# Radio.net
KiCad netlist of a schematic drawn in Altium Designer
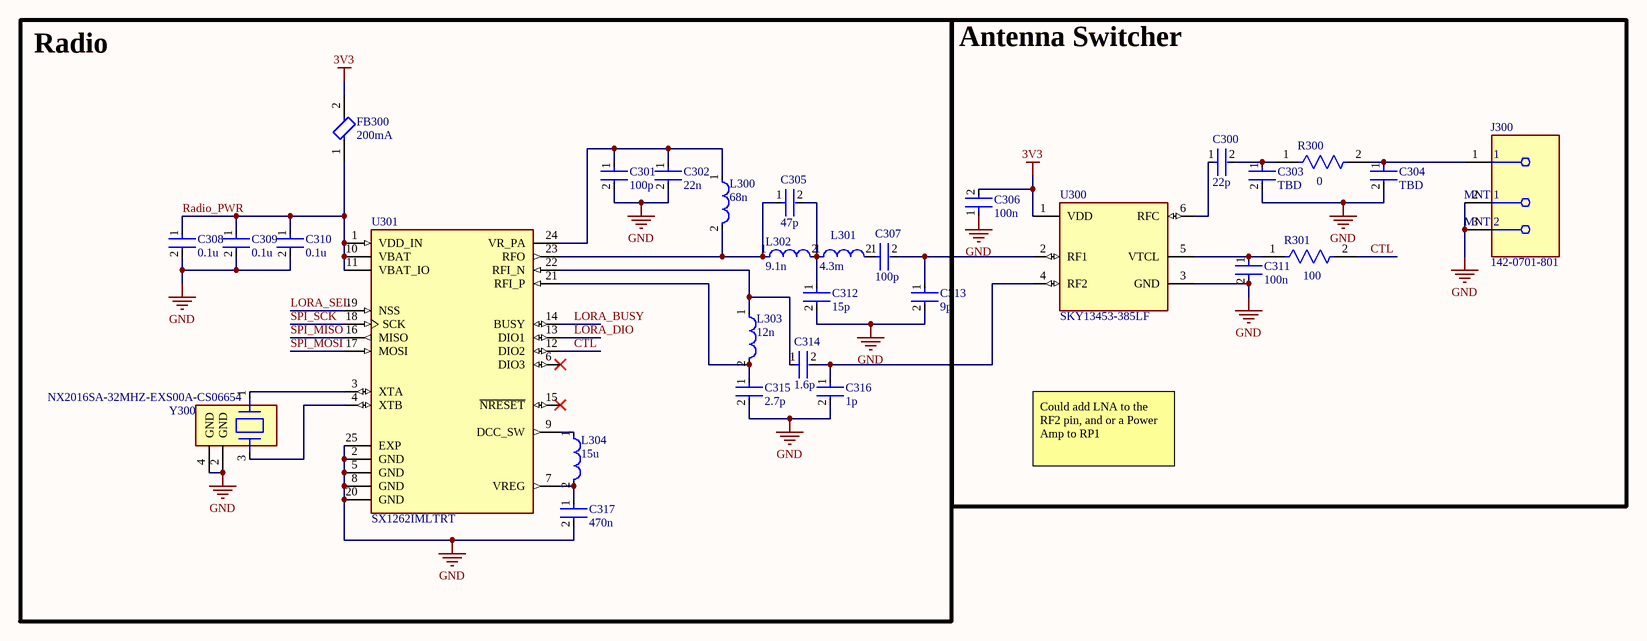
[diagram p0: Radio.SchDoc]

(export (version "E")
  (design (tool "Eeschema 10.0.6"))
  (components
    (comp (ref "C300")
      (value "CL10C681JB8NFNC")
      (footprint "FP-CL10-IPC_A")
      (description "Cap Ceramic 680pF 50V C0G ±5% Pad SMD 0603 +125°C T/R")
      (fields (field (name "CAPACITANCE") "22p") (field (name "TOLERANCE") "5%"))
      (libsource (lib "Altium Content Vault") (part "b4654b650e69147ec39a6b967a45e02"))
    )
    (comp (ref "C301")
      (value "CL10C681JB8NFNC")
      (footprint "FP-CL10-IPC_A")
      (description "Cap Ceramic 680pF 50V C0G ±5% Pad SMD 0603 +125°C T/R")
      (fields (field (name "CAPACITANCE") "100p") (field (name "TOLERANCE") "5%"))
      (libsource (lib "Altium Content Vault") (part "b4654b650e69147ec39a6b967a45e02"))
    )
    (comp (ref "C302")
      (value "CL10C681JB8NFNC")
      (footprint "FP-CL10-IPC_A")
      (description "Cap Ceramic 680pF 50V C0G ±5% Pad SMD 0603 +125°C T/R")
      (fields (field (name "CAPACITANCE") "22n") (field (name "TOLERANCE") "5%"))
      (libsource (lib "Altium Content Vault") (part "b4654b650e69147ec39a6b967a45e02"))
    )
    (comp (ref "C303")
      (value "CL10C681JB8NFNC")
      (footprint "FP-CL10-IPC_A")
      (description "Cap Ceramic 680pF 50V C0G ±5% Pad SMD 0603 +125°C T/R")
      (fields (field (name "CAPACITANCE") "TBD") (field (name "TOLERANCE") "5%"))
      (libsource (lib "Altium Content Vault") (part "b4654b650e69147ec39a6b967a45e02"))
    )
    (comp (ref "C304")
      (value "CL10C681JB8NFNC")
      (footprint "FP-CL10-IPC_A")
      (description "Cap Ceramic 680pF 50V C0G ±5% Pad SMD 0603 +125°C T/R")
      (fields (field (name "CAPACITANCE") "TBD") (field (name "TOLERANCE") "5%"))
      (libsource (lib "Altium Content Vault") (part "b4654b650e69147ec39a6b967a45e02"))
    )
    (comp (ref "C305")
      (value "CL10C681JB8NFNC")
      (footprint "FP-CL10-IPC_A")
      (description "Cap Ceramic 680pF 50V C0G ±5% Pad SMD 0603 +125°C T/R")
      (fields (field (name "CAPACITANCE") "47p") (field (name "TOLERANCE") "5%"))
      (libsource (lib "Altium Content Vault") (part "b4654b650e69147ec39a6b967a45e02"))
    )
    (comp (ref "C306")
      (value "CL10C681JB8NFNC")
      (footprint "FP-CL10-IPC_A")
      (description "Cap Ceramic 680pF 50V C0G ±5% Pad SMD 0603 +125°C T/R")
      (fields (field (name "CAPACITANCE") "100n") (field (name "TOLERANCE") "5%"))
      (libsource (lib "Altium Content Vault") (part "b4654b650e69147ec39a6b967a45e02"))
    )
    (comp (ref "C307")
      (value "CL10C681JB8NFNC")
      (footprint "FP-CL10-IPC_A")
      (description "Cap Ceramic 680pF 50V C0G ±5% Pad SMD 0603 +125°C T/R")
      (fields (field (name "CAPACITANCE") "100p") (field (name "TOLERANCE") "5%"))
      (libsource (lib "Altium Content Vault") (part "b4654b650e69147ec39a6b967a45e02"))
    )
    (comp (ref "C308")
      (value "CL10C681JB8NFNC")
      (footprint "FP-CL10-IPC_A")
      (description "Cap Ceramic 680pF 50V C0G ±5% Pad SMD 0603 +125°C T/R")
      (fields (field (name "CAPACITANCE") "0.1u") (field (name "TOLERANCE") "5%"))
      (libsource (lib "Altium Content Vault") (part "b4654b650e69147ec39a6b967a45e02"))
    )
    (comp (ref "C309")
      (value "CL10C681JB8NFNC")
      (footprint "FP-CL10-IPC_A")
      (description "Cap Ceramic 680pF 50V C0G ±5% Pad SMD 0603 +125°C T/R")
      (fields (field (name "CAPACITANCE") "0.1u") (field (name "TOLERANCE") "5%"))
      (libsource (lib "Altium Content Vault") (part "b4654b650e69147ec39a6b967a45e02"))
    )
    (comp (ref "C310")
      (value "CL10C681JB8NFNC")
      (footprint "FP-CL10-IPC_A")
      (description "Cap Ceramic 680pF 50V C0G ±5% Pad SMD 0603 +125°C T/R")
      (fields (field (name "CAPACITANCE") "0.1u") (field (name "TOLERANCE") "5%"))
      (libsource (lib "Altium Content Vault") (part "b4654b650e69147ec39a6b967a45e02"))
    )
    (comp (ref "C311")
      (value "CL10C681JB8NFNC")
      (footprint "FP-CL10-IPC_A")
      (description "Cap Ceramic 680pF 50V C0G ±5% Pad SMD 0603 +125°C T/R")
      (fields (field (name "CAPACITANCE") "100n") (field (name "TOLERANCE") "5%"))
      (libsource (lib "Altium Content Vault") (part "b4654b650e69147ec39a6b967a45e02"))
    )
    (comp (ref "C312")
      (value "CL10C681JB8NFNC")
      (footprint "FP-CL10-IPC_A")
      (description "Cap Ceramic 680pF 50V C0G ±5% Pad SMD 0603 +125°C T/R")
      (fields (field (name "CAPACITANCE") "15p") (field (name "TOLERANCE") "5%"))
      (libsource (lib "Altium Content Vault") (part "b4654b650e69147ec39a6b967a45e02"))
    )
    (comp (ref "C313")
      (value "CL10C681JB8NFNC")
      (footprint "FP-CL10-IPC_A")
      (description "Cap Ceramic 680pF 50V C0G ±5% Pad SMD 0603 +125°C T/R")
      (fields (field (name "CAPACITANCE") "9p") (field (name "TOLERANCE") "5%"))
      (libsource (lib "Altium Content Vault") (part "b4654b650e69147ec39a6b967a45e02"))
    )
    (comp (ref "C314")
      (value "CL10C681JB8NFNC")
      (footprint "FP-CL10-IPC_A")
      (description "Cap Ceramic 680pF 50V C0G ±5% Pad SMD 0603 +125°C T/R")
      (fields (field (name "CAPACITANCE") "1.6p") (field (name "TOLERANCE") "5%"))
      (libsource (lib "Altium Content Vault") (part "b4654b650e69147ec39a6b967a45e02"))
    )
    (comp (ref "C315")
      (value "CL10C681JB8NFNC")
      (footprint "FP-CL10-IPC_A")
      (description "Cap Ceramic 680pF 50V C0G ±5% Pad SMD 0603 +125°C T/R")
      (fields (field (name "CAPACITANCE") "2.7p") (field (name "TOLERANCE") "5%"))
      (libsource (lib "Altium Content Vault") (part "b4654b650e69147ec39a6b967a45e02"))
    )
    (comp (ref "C316")
      (value "CL10C681JB8NFNC")
      (footprint "FP-CL10-IPC_A")
      (description "Cap Ceramic 680pF 50V C0G ±5% Pad SMD 0603 +125°C T/R")
      (fields (field (name "CAPACITANCE") "1p") (field (name "TOLERANCE") "5%"))
      (libsource (lib "Altium Content Vault") (part "b4654b650e69147ec39a6b967a45e02"))
    )
    (comp (ref "C317")
      (value "CL10C681JB8NFNC")
      (footprint "FP-CL10-IPC_A")
      (description "Cap Ceramic 680pF 50V C0G ±5% Pad SMD 0603 +125°C T/R")
      (fields (field (name "CAPACITANCE") "470n") (field (name "TOLERANCE") "5%"))
      (libsource (lib "Altium Content Vault") (part "b4654b650e69147ec39a6b967a45e02"))
    )
    (comp (ref "FB300")
      (value "200mA")
      (footprint "FP-BLM18-0_15-t0_8-IPC_B")
      (description "Chip Ferrite Bead, 0603, 120Ω @ 100MHz, 0.4Ω, 25%, 300mA")
      (fields (field (name "TOLERANCE") "25%"))
      (libsource (lib "Altium Content Vault") (part "5f30dd21d616792df468990f7003faa"))
    )
    (comp (ref "J300")
      (value "142-0701-801")
      (footprint "FP-142-0701-801-MFG")
      (description "CONN SMA JACK STR 50OHM EDGE MNT")
      (libsource (lib "Altium Content Vault") (part "89929399afe843c8b6880c6cbd0f99a"))
    )
    (comp (ref "L300")
      (value "68n")
      (footprint "FP-LQM18NN_00-IPC_B")
      (description "Multilayer Type Inductor for General Circuits, 0603 (1608), 2200nH, 10%, 1.15Ω, 15mA")
      (fields (field (name "TOLERANCE") "10%"))
      (libsource (lib "Altium Content Vault") (part "725321dda6339637d4d059423bc1c3c"))
    )
    (comp (ref "L301")
      (value "4.3m")
      (footprint "FP-LQM18NN_00-IPC_B")
      (description "Multilayer Type Inductor for General Circuits, 0603 (1608), 2200nH, 10%, 1.15Ω, 15mA")
      (fields (field (name "TOLERANCE") "10%"))
      (libsource (lib "Altium Content Vault") (part "725321dda6339637d4d059423bc1c3c"))
    )
    (comp (ref "L302")
      (value "9.1n")
      (footprint "FP-LQM18NN_00-IPC_B")
      (description "Multilayer Type Inductor for General Circuits, 0603 (1608), 2200nH, 10%, 1.15Ω, 15mA")
      (fields (field (name "TOLERANCE") "10%"))
      (libsource (lib "Altium Content Vault") (part "725321dda6339637d4d059423bc1c3c"))
    )
    (comp (ref "L303")
      (value "12n")
      (footprint "FP-LQM18NN_00-IPC_B")
      (description "Multilayer Type Inductor for General Circuits, 0603 (1608), 2200nH, 10%, 1.15Ω, 15mA")
      (fields (field (name "TOLERANCE") "10%"))
      (libsource (lib "Altium Content Vault") (part "725321dda6339637d4d059423bc1c3c"))
    )
    (comp (ref "L304")
      (value "15u")
      (footprint "FP-LQM18NN_00-IPC_B")
      (description "Multilayer Type Inductor for General Circuits, 0603 (1608), 2200nH, 10%, 1.15Ω, 15mA")
      (fields (field (name "TOLERANCE") "10%"))
      (libsource (lib "Altium Content Vault") (part "725321dda6339637d4d059423bc1c3c"))
    )
    (comp (ref "R300")
      (value "0")
      (footprint "FP-CPF0603-MFG")
      (description "RES SMD 2.15KΩ 0.1% 1/16W 0603")
      (fields
        (field (name "MANUFACTURER") "TE Connectivity")
        (field (name "OCTOPART") "https://octopart.com/cpf0603b2k15e1-te+connectivity-22739551")
      )
      (libsource (lib "Altium Content Vault") (part "1029c3af85768c4190bb7ad29bc67b5"))
    )
    (comp (ref "R301")
      (value "100")
      (footprint "FP-CPF0603-MFG")
      (description "RES SMD 2.15KΩ 0.1% 1/16W 0603")
      (fields
        (field (name "MANUFACTURER") "TE Connectivity")
        (field (name "OCTOPART") "https://octopart.com/cpf0603b2k15e1-te+connectivity-22739551")
      )
      (libsource (lib "Altium Content Vault") (part "1029c3af85768c4190bb7ad29bc67b5"))
    )
    (comp (ref "U300")
      (value "SKY13453-385LF")
      (footprint "IC_SKY13453-385LF")
      (description "RF Switch IC WLAN SPDT 6 GHz 50Ohm 6-QFN (1x1)")
      (fields (field (name "MF") "Skyworks Solutions"))
      (libsource (lib "Colin Sutter") (part "SKY13453-385LF"))
    )
    (comp (ref "U301")
      (value "SX1262IMLTRT")
      (footprint "QFN50P400X400X100-25N")
      (description "IC RF TxRx Only General ISM < 1GHz LoRaWAN 150MHz ~ 960MHz 24-VFQFN Exposed Pad")
      (fields (field (name "MF") "Semtech Corporation"))
      (libsource (lib "Colin Sutter") (part "SX1262IMLTRT"))
    )
    (comp (ref "Y300")
      (value "NX2016SA-32MHZ-EXS00A-CS06654")
      (footprint "FP-NX2016SA-MFG")
      (description "CRYSTAL 32.0000MHZ 8PF SMD")
      (libsource (lib "Altium Content Vault") (part "0d11ad3ca7be055efd3b4f344707230"))
    )
  )
  (nets
    (net (code "1") (name "/CTL") (class "Default")
      (node (ref "R301") (pin "2") (pinfunction "2_2") (pintype "passive"))
      (node (ref "U301") (pin "12") (pinfunction "DIO2_12") (pintype "bidirectional"))
    )
    (net (code "2") (name "/LORA_BUSY") (class "Default")
      (node (ref "U301") (pin "14") (pinfunction "BUSY_14") (pintype "bidirectional"))
    )
    (net (code "3") (name "/LORA_DIO") (class "Default")
      (node (ref "U301") (pin "13") (pinfunction "DIO1_13") (pintype "bidirectional"))
    )
    (net (code "4") (name "/LORA_SEL") (class "Default")
      (node (ref "U301") (pin "19") (pinfunction "NSS_19") (pintype "input"))
    )
    (net (code "5") (name "/Radio_PWR") (class "Default")
      (node (ref "C308") (pin "1") (pinfunction "1_1") (pintype "passive"))
      (node (ref "C309") (pin "1") (pinfunction "1_1") (pintype "passive"))
      (node (ref "C310") (pin "1") (pinfunction "1_1") (pintype "passive"))
      (node (ref "FB300") (pin "1") (pinfunction "1_1") (pintype "passive"))
      (node (ref "U301") (pin "1") (pinfunction "VDD_IN_1") (pintype "input"))
      (node (ref "U301") (pin "10") (pinfunction "VBAT_10") (pintype "power_in"))
      (node (ref "U301") (pin "11") (pinfunction "VBAT_IO_11") (pintype "power_in"))
    )
    (net (code "6") (name "/SPI_MISO") (class "Default")
      (node (ref "U301") (pin "16") (pinfunction "MISO_16") (pintype "output"))
    )
    (net (code "7") (name "/SPI_MOSI") (class "Default")
      (node (ref "U301") (pin "17") (pinfunction "MOSI_17") (pintype "input"))
    )
    (net (code "8") (name "/SPI_SCK") (class "Default")
      (node (ref "U301") (pin "18") (pinfunction "SCK_18") (pintype "input"))
    )
    (net (code "9") (name "3V3") (class "Default")
      (node (ref "C306") (pin "2") (pinfunction "2_2") (pintype "passive"))
      (node (ref "FB300") (pin "2") (pinfunction "2_2") (pintype "passive"))
      (node (ref "U300") (pin "1") (pinfunction "VDD_1") (pintype "power_in"))
    )
    (net (code "10") (name "GND") (class "Default")
      (node (ref "C301") (pin "2") (pinfunction "2_2") (pintype "passive"))
      (node (ref "C302") (pin "2") (pinfunction "2_2") (pintype "passive"))
      (node (ref "C303") (pin "2") (pinfunction "2_2") (pintype "passive"))
      (node (ref "C304") (pin "2") (pinfunction "2_2") (pintype "passive"))
      (node (ref "C306") (pin "1") (pinfunction "1_1") (pintype "passive"))
      (node (ref "C308") (pin "2") (pinfunction "2_2") (pintype "passive"))
      (node (ref "C309") (pin "2") (pinfunction "2_2") (pintype "passive"))
      (node (ref "C310") (pin "2") (pinfunction "2_2") (pintype "passive"))
      (node (ref "C311") (pin "2") (pinfunction "2_2") (pintype "passive"))
      (node (ref "C312") (pin "2") (pinfunction "2_2") (pintype "passive"))
      (node (ref "C313") (pin "2") (pinfunction "2_2") (pintype "passive"))
      (node (ref "C315") (pin "2") (pinfunction "2_2") (pintype "passive"))
      (node (ref "C316") (pin "2") (pinfunction "2_2") (pintype "passive"))
      (node (ref "C317") (pin "2") (pinfunction "2_2") (pintype "passive"))
      (node (ref "J300") (pin "2") (pinfunction "MNT_1_2") (pintype "passive"))
      (node (ref "J300") (pin "3") (pinfunction "MNT_2_3") (pintype "passive"))
      (node (ref "U300") (pin "3") (pinfunction "GND_3") (pintype "power_in"))
      (node (ref "U301") (pin "2") (pinfunction "GND_2") (pintype "power_in"))
      (node (ref "U301") (pin "20") (pinfunction "GND_20") (pintype "power_in"))
      (node (ref "U301") (pin "25") (pinfunction "EXP_25") (pintype "power_in"))
      (node (ref "U301") (pin "5") (pinfunction "GND_5") (pintype "power_in"))
      (node (ref "U301") (pin "8") (pinfunction "GND_8") (pintype "power_in"))
      (node (ref "Y300") (pin "2") (pinfunction "GND_2") (pintype "power_in"))
      (node (ref "Y300") (pin "4") (pinfunction "GND_4") (pintype "power_in"))
    )
    (net (code "11") (name "Net-(C300-Pad2)") (class "Default")
      (node (ref "C300") (pin "2") (pinfunction "2_2") (pintype "passive"))
      (node (ref "C303") (pin "1") (pinfunction "1_1") (pintype "passive"))
      (node (ref "R300") (pin "1") (pinfunction "1_1") (pintype "passive"))
    )
    (net (code "12") (name "Net-(C304-Pad1)") (class "Default")
      (node (ref "C304") (pin "1") (pinfunction "1_1") (pintype "passive"))
      (node (ref "J300") (pin "1") (pinfunction "1_1") (pintype "passive"))
      (node (ref "R300") (pin "2") (pinfunction "2_2") (pintype "passive"))
    )
    (net (code "13") (name "Net-(C305-Pad2)") (class "Default")
      (node (ref "C305") (pin "2") (pinfunction "2_2") (pintype "passive"))
      (node (ref "C312") (pin "1") (pinfunction "1_1") (pintype "passive"))
      (node (ref "L301") (pin "1") (pinfunction "1_1") (pintype "passive"))
      (node (ref "L302") (pin "2") (pinfunction "2_2") (pintype "passive"))
    )
    (net (code "14") (name "Net-(C307-Pad1)") (class "Default")
      (node (ref "C307") (pin "1") (pinfunction "1_1") (pintype "passive"))
      (node (ref "L301") (pin "2") (pinfunction "2_2") (pintype "passive"))
    )
    (net (code "15") (name "Net-(U300-RF1)") (class "Default")
      (node (ref "C307") (pin "2") (pinfunction "2_2") (pintype "passive"))
      (node (ref "C313") (pin "1") (pinfunction "1_1") (pintype "passive"))
      (node (ref "U300") (pin "2") (pinfunction "RF1_2") (pintype "bidirectional"))
    )
    (net (code "16") (name "Net-(U300-RF2)") (class "Default")
      (node (ref "C314") (pin "2") (pinfunction "2_2") (pintype "passive"))
      (node (ref "C316") (pin "1") (pinfunction "1_1") (pintype "passive"))
      (node (ref "U300") (pin "4") (pinfunction "RF2_4") (pintype "bidirectional"))
    )
    (net (code "17") (name "Net-(U300-RFC)") (class "Default")
      (node (ref "C300") (pin "1") (pinfunction "1_1") (pintype "passive"))
      (node (ref "U300") (pin "6") (pinfunction "RFC_6") (pintype "bidirectional"))
    )
    (net (code "18") (name "Net-(U300-VTCL)") (class "Default")
      (node (ref "C311") (pin "1") (pinfunction "1_1") (pintype "passive"))
      (node (ref "R301") (pin "1") (pinfunction "1_1") (pintype "passive"))
      (node (ref "U300") (pin "5") (pinfunction "VTCL_5") (pintype "passive"))
    )
    (net (code "19") (name "Net-(U301-DCC_SW)") (class "Default")
      (node (ref "L304") (pin "1") (pinfunction "1_1") (pintype "passive"))
      (node (ref "U301") (pin "9") (pinfunction "DCC_SW_9") (pintype "output"))
    )
    (net (code "20") (name "Net-(U301-RFI_N)") (class "Default")
      (node (ref "C314") (pin "1") (pinfunction "1_1") (pintype "passive"))
      (node (ref "L303") (pin "1") (pinfunction "1_1") (pintype "passive"))
      (node (ref "U301") (pin "22") (pinfunction "RFI_N_22") (pintype "input"))
    )
    (net (code "21") (name "Net-(U301-RFI_P)") (class "Default")
      (node (ref "C315") (pin "1") (pinfunction "1_1") (pintype "passive"))
      (node (ref "L303") (pin "2") (pinfunction "2_2") (pintype "passive"))
      (node (ref "U301") (pin "21") (pinfunction "RFI_P_21") (pintype "input"))
    )
    (net (code "22") (name "Net-(U301-RFO)") (class "Default")
      (node (ref "C305") (pin "1") (pinfunction "1_1") (pintype "passive"))
      (node (ref "L300") (pin "2") (pinfunction "2_2") (pintype "passive"))
      (node (ref "L302") (pin "1") (pinfunction "1_1") (pintype "passive"))
      (node (ref "U301") (pin "23") (pinfunction "RFO_23") (pintype "output"))
    )
    (net (code "23") (name "Net-(U301-VREG)") (class "Default")
      (node (ref "C317") (pin "1") (pinfunction "1_1") (pintype "passive"))
      (node (ref "L304") (pin "2") (pinfunction "2_2") (pintype "passive"))
      (node (ref "U301") (pin "7") (pinfunction "VREG_7") (pintype "output"))
    )
    (net (code "24") (name "Net-(U301-VR_PA)") (class "Default")
      (node (ref "C301") (pin "1") (pinfunction "1_1") (pintype "passive"))
      (node (ref "C302") (pin "1") (pinfunction "1_1") (pintype "passive"))
      (node (ref "L300") (pin "1") (pinfunction "1_1") (pintype "passive"))
      (node (ref "U301") (pin "24") (pinfunction "VR_PA_24") (pintype "power_in"))
    )
    (net (code "25") (name "Net-(U301-XTA)") (class "Default")
      (node (ref "U301") (pin "3") (pinfunction "XTA_3") (pintype "bidirectional"))
      (node (ref "Y300") (pin "1") (pinfunction "1_1") (pintype "passive"))
    )
    (net (code "26") (name "Net-(U301-XTB)") (class "Default")
      (node (ref "U301") (pin "4") (pinfunction "XTB_4") (pintype "bidirectional"))
      (node (ref "Y300") (pin "3") (pinfunction "3_3") (pintype "passive"))
    )
    (net (code "27") (name "unconnected-(U301-DIO3-Pad6)") (class "Default")
      (node (ref "U301") (pin "6") (pinfunction "DIO3_6") (pintype "bidirectional+no_connect"))
    )
    (net (code "28") (name "unconnected-(U301-~{NRESET}-Pad15)") (class "Default")
      (node (ref "U301") (pin "15") (pinfunction "~{NRESET}_15") (pintype "bidirectional+no_connect"))
    )
  )
)
